# PowerTest.net
KiCad netlist of a schematic drawn in EAGLE
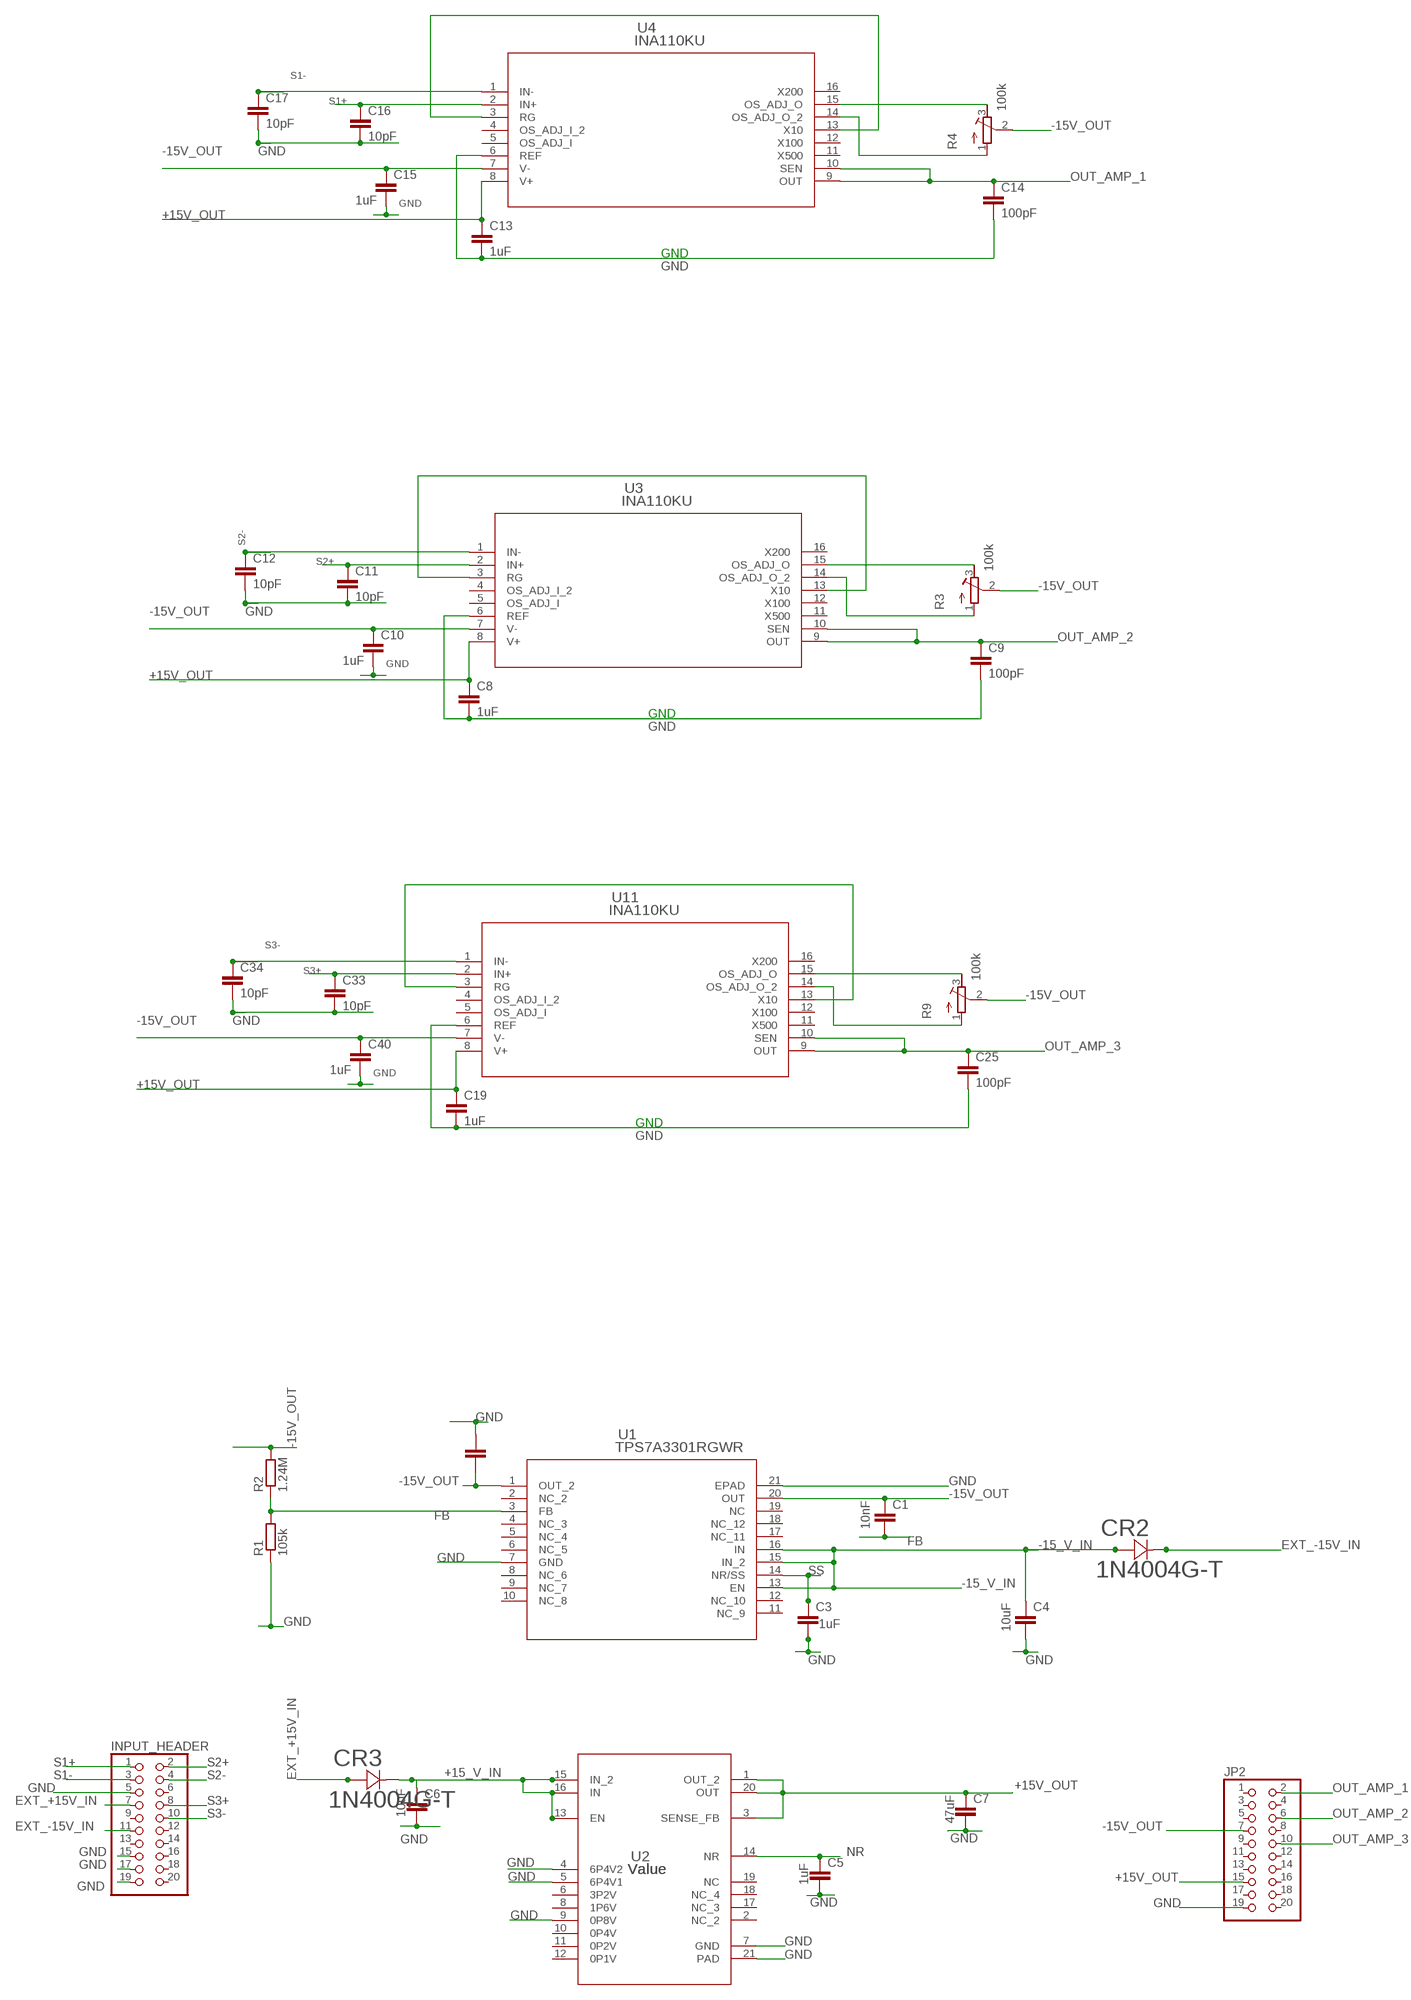
[diagram p0: schematic, sheet 1]

(export (version "E")
  (design (tool "Eeschema 10.0.6"))
  (components
    (comp (ref "C1")
      (value "10nF")
      (footprint "eagle-import:C1210")
      (libsource (lib "eagle-import") (part "C-EUC1210"))
    )
    (comp (ref "C3")
      (value "1uF")
      (footprint "eagle-import:C1210")
      (libsource (lib "eagle-import") (part "C-EUC1210"))
    )
    (comp (ref "C4")
      (value "10uF")
      (footprint "eagle-import:C1210")
      (libsource (lib "eagle-import") (part "C-EUC1210"))
    )
    (comp (ref "C5")
      (value "1uF")
      (footprint "eagle-import:C1210")
      (libsource (lib "eagle-import") (part "C-EUC1210"))
    )
    (comp (ref "C6")
      (value "10uF")
      (footprint "eagle-import:C1210")
      (libsource (lib "eagle-import") (part "C-EUC1210"))
    )
    (comp (ref "C7")
      (value "47uF")
      (footprint "eagle-import:C1210")
      (libsource (lib "eagle-import") (part "C-EUC1210"))
    )
    (comp (ref "C8")
      (value "1uF")
      (footprint "eagle-import:C1210")
      (libsource (lib "eagle-import") (part "C-EUC1210"))
    )
    (comp (ref "C9")
      (value "100pF")
      (footprint "eagle-import:C1210")
      (libsource (lib "eagle-import") (part "C-EUC1210"))
    )
    (comp (ref "C10")
      (value "1uF")
      (footprint "eagle-import:C1210")
      (libsource (lib "eagle-import") (part "C-EUC1210"))
    )
    (comp (ref "C11")
      (value "10pF")
      (footprint "eagle-import:C1210")
      (libsource (lib "eagle-import") (part "C-EUC1210"))
    )
    (comp (ref "C12")
      (value "10pF")
      (footprint "eagle-import:C1210")
      (libsource (lib "eagle-import") (part "C-EUC1210"))
    )
    (comp (ref "C13")
      (value "1uF")
      (footprint "eagle-import:C1210")
      (libsource (lib "eagle-import") (part "C-EUC1210"))
    )
    (comp (ref "C14")
      (value "100pF")
      (footprint "eagle-import:C1210")
      (libsource (lib "eagle-import") (part "C-EUC1210"))
    )
    (comp (ref "C15")
      (value "1uF")
      (footprint "eagle-import:C1210")
      (libsource (lib "eagle-import") (part "C-EUC1210"))
    )
    (comp (ref "C16")
      (value "10pF")
      (footprint "eagle-import:C1210")
      (libsource (lib "eagle-import") (part "C-EUC1210"))
    )
    (comp (ref "C17")
      (value "10pF")
      (footprint "eagle-import:C1210")
      (libsource (lib "eagle-import") (part "C-EUC1210"))
    )
    (comp (ref "C19")
      (value "1uF")
      (footprint "eagle-import:C1210")
      (libsource (lib "eagle-import") (part "C-EUC1210"))
    )
    (comp (ref "C25")
      (value "100pF")
      (footprint "eagle-import:C1210")
      (libsource (lib "eagle-import") (part "C-EUC1210"))
    )
    (comp (ref "C33")
      (value "10pF")
      (footprint "eagle-import:C1210")
      (libsource (lib "eagle-import") (part "C-EUC1210"))
    )
    (comp (ref "C34")
      (value "10pF")
      (footprint "eagle-import:C1210")
      (libsource (lib "eagle-import") (part "C-EUC1210"))
    )
    (comp (ref "C40")
      (value "1uF")
      (footprint "eagle-import:C1210")
      (libsource (lib "eagle-import") (part "C-EUC1210"))
    )
    (comp (ref "C55")
      (value "47uF")
      (footprint "eagle-import:C1210")
      (libsource (lib "eagle-import") (part "C-EUC1210"))
    )
    (comp (ref "CR2")
      (value "1N4004G-T")
      (footprint "eagle-import:DO-41")
      (fields (field (name "MANUFACTURER_PART_NUMBER") "1N4004GT"))
      (libsource (lib "eagle-import") (part "1N4004G-T"))
    )
    (comp (ref "CR3")
      (value "1N4004G-T")
      (footprint "eagle-import:DO-41")
      (fields (field (name "MANUFACTURER_PART_NUMBER") "1N4004GT"))
      (libsource (lib "eagle-import") (part "1N4004G-T"))
    )
    (comp (ref "INPUT_HEADER")
      (value "PINHD-2X10")
      (footprint "eagle-import:2X10")
      (libsource (lib "eagle-import") (part "PINHD-2X10"))
    )
    (comp (ref "JP2")
      (value "PINHD-2X10")
      (footprint "eagle-import:2X10")
      (libsource (lib "eagle-import") (part "PINHD-2X10"))
    )
    (comp (ref "R1")
      (value "105k")
      (footprint "eagle-import:RESC2012X65")
      (libsource (lib "eagle-import") (part "RCHIP-0805(2012-METRIC)_"))
    )
    (comp (ref "R2")
      (value "1.24M")
      (footprint "eagle-import:RESC2012X65")
      (libsource (lib "eagle-import") (part "RCHIP-0805(2012-METRIC)_"))
    )
    (comp (ref "R3")
      (value "100k")
      (footprint "eagle-import:RTRIM3296Y")
      (libsource (lib "eagle-import") (part "R-TRIMM3296Y"))
    )
    (comp (ref "R4")
      (value "100k")
      (footprint "eagle-import:RTRIM3296Y")
      (libsource (lib "eagle-import") (part "R-TRIMM3296Y"))
    )
    (comp (ref "R9")
      (value "100k")
      (footprint "eagle-import:RTRIM3296Y")
      (libsource (lib "eagle-import") (part "R-TRIMM3296Y"))
    )
    (comp (ref "U1")
      (value "TPS7A3301RGWR")
      (footprint "eagle-import:RGW0020A")
      (fields
        (field (name "GENERIC_PART_NUMBER") "TPS7A3301")
        (field (name "MANUFACTURER") "Texas Instruments")
      )
      (libsource (lib "eagle-import") (part "TPS7A3301RGWR"))
    )
    (comp (ref "U2")
      (value "Value")
      (footprint "eagle-import:RGW0020A")
      (fields (field (name "MANUFACTURER") "Texas Instruments") (field (name "PARTNUMBER") "TPS7A4701RGWR"))
      (libsource (lib "eagle-import") (part "TPS7A4700RGWR"))
    )
    (comp (ref "U3")
      (value "INA110KU")
      (footprint "eagle-import:SO-G16G6.9")
      (libsource (lib "eagle-import") (part "INA110KU"))
    )
    (comp (ref "U4")
      (value "INA110KU")
      (footprint "eagle-import:SO-G16G6.9")
      (libsource (lib "eagle-import") (part "INA110KU"))
    )
    (comp (ref "U11")
      (value "INA110KU")
      (footprint "eagle-import:SO-G16G6.9")
      (libsource (lib "eagle-import") (part "INA110KU"))
    )
  )
  (nets
    (net (code "1") (name "/+15V_OUT") (class "Default")
      (node (ref "C13") (pin "1") (pinfunction "1_1") (pintype "passive"))
      (node (ref "C19") (pin "1") (pinfunction "1_1") (pintype "passive"))
      (node (ref "C7") (pin "1") (pinfunction "1_1") (pintype "passive"))
      (node (ref "C8") (pin "1") (pinfunction "1_1") (pintype "passive"))
      (node (ref "JP2") (pin "15") (pinfunction "15_15") (pintype "passive"))
      (node (ref "U11") (pin "8") (pinfunction "V+_8") (pintype "power_in"))
      (node (ref "U2") (pin "1") (pinfunction "OUT_2_1") (pintype "power_in"))
      (node (ref "U2") (pin "20") (pinfunction "OUT_20") (pintype "power_in"))
      (node (ref "U2") (pin "3") (pinfunction "SENSE_FB_3") (pintype "input"))
      (node (ref "U3") (pin "8") (pinfunction "V+_8") (pintype "power_in"))
      (node (ref "U4") (pin "8") (pinfunction "V+_8") (pintype "power_in"))
    )
    (net (code "2") (name "/+15_V_IN") (class "Default")
      (node (ref "C6") (pin "1") (pinfunction "1_1") (pintype "passive"))
      (node (ref "CR3") (pin "1") (pinfunction "1_1") (pintype "passive"))
      (node (ref "U2") (pin "13") (pinfunction "EN_13") (pintype "input"))
      (node (ref "U2") (pin "15") (pinfunction "IN_2_15") (pintype "power_in"))
      (node (ref "U2") (pin "16") (pinfunction "IN_16") (pintype "power_in"))
    )
    (net (code "3") (name "/-15V_OUT") (class "Default")
      (node (ref "C1") (pin "1") (pinfunction "1_1") (pintype "passive"))
      (node (ref "C10") (pin "1") (pinfunction "1_1") (pintype "passive"))
      (node (ref "C15") (pin "1") (pinfunction "1_1") (pintype "passive"))
      (node (ref "C40") (pin "1") (pinfunction "1_1") (pintype "passive"))
      (node (ref "C55") (pin "2") (pinfunction "2_2") (pintype "passive"))
      (node (ref "JP2") (pin "7") (pinfunction "7_7") (pintype "passive"))
      (node (ref "R2") (pin "2") (pinfunction "2_2") (pintype "passive"))
      (node (ref "R3") (pin "2") (pinfunction "S_2") (pintype "passive"))
      (node (ref "R4") (pin "2") (pinfunction "S_2") (pintype "passive"))
      (node (ref "R9") (pin "2") (pinfunction "S_2") (pintype "passive"))
      (node (ref "U1") (pin "1") (pinfunction "OUT_2_1") (pintype "output"))
      (node (ref "U1") (pin "20") (pinfunction "OUT_20") (pintype "output"))
      (node (ref "U11") (pin "7") (pinfunction "V-_7") (pintype "power_in"))
      (node (ref "U3") (pin "7") (pinfunction "V-_7") (pintype "power_in"))
      (node (ref "U4") (pin "7") (pinfunction "V-_7") (pintype "power_in"))
    )
    (net (code "4") (name "/-15_V_IN") (class "Default")
      (node (ref "C4") (pin "1") (pinfunction "1_1") (pintype "passive"))
      (node (ref "CR2") (pin "2") (pinfunction "2_2") (pintype "passive"))
      (node (ref "U1") (pin "13") (pinfunction "EN_13") (pintype "passive"))
      (node (ref "U1") (pin "15") (pinfunction "IN_2_15") (pintype "input"))
      (node (ref "U1") (pin "16") (pinfunction "IN_16") (pintype "input"))
    )
    (net (code "5") (name "/EXT_+15V_IN") (class "Default")
      (node (ref "CR3") (pin "2") (pinfunction "2_2") (pintype "passive"))
      (node (ref "INPUT_HEADER") (pin "7") (pinfunction "7_7") (pintype "passive"))
    )
    (net (code "6") (name "/EXT_-15V_IN") (class "Default")
      (node (ref "CR2") (pin "1") (pinfunction "1_1") (pintype "passive"))
      (node (ref "INPUT_HEADER") (pin "11") (pinfunction "11_11") (pintype "passive"))
    )
    (net (code "7") (name "/FB") (class "Default")
      (node (ref "C1") (pin "2") (pinfunction "2_2") (pintype "passive"))
      (node (ref "R1") (pin "2") (pinfunction "2_2") (pintype "passive"))
      (node (ref "R2") (pin "1") (pinfunction "1_1") (pintype "passive"))
      (node (ref "U1") (pin "3") (pinfunction "FB_3") (pintype "passive"))
    )
    (net (code "8") (name "/GND") (class "Default")
      (node (ref "C10") (pin "2") (pinfunction "2_2") (pintype "passive"))
      (node (ref "C11") (pin "2") (pinfunction "2_2") (pintype "passive"))
      (node (ref "C12") (pin "2") (pinfunction "2_2") (pintype "passive"))
      (node (ref "C13") (pin "2") (pinfunction "2_2") (pintype "passive"))
      (node (ref "C14") (pin "2") (pinfunction "2_2") (pintype "passive"))
      (node (ref "C15") (pin "2") (pinfunction "2_2") (pintype "passive"))
      (node (ref "C16") (pin "2") (pinfunction "2_2") (pintype "passive"))
      (node (ref "C17") (pin "2") (pinfunction "2_2") (pintype "passive"))
      (node (ref "C19") (pin "2") (pinfunction "2_2") (pintype "passive"))
      (node (ref "C25") (pin "2") (pinfunction "2_2") (pintype "passive"))
      (node (ref "C3") (pin "2") (pinfunction "2_2") (pintype "passive"))
      (node (ref "C33") (pin "2") (pinfunction "2_2") (pintype "passive"))
      (node (ref "C34") (pin "2") (pinfunction "2_2") (pintype "passive"))
      (node (ref "C4") (pin "2") (pinfunction "2_2") (pintype "passive"))
      (node (ref "C40") (pin "2") (pinfunction "2_2") (pintype "passive"))
      (node (ref "C5") (pin "2") (pinfunction "2_2") (pintype "passive"))
      (node (ref "C55") (pin "1") (pinfunction "1_1") (pintype "passive"))
      (node (ref "C6") (pin "2") (pinfunction "2_2") (pintype "passive"))
      (node (ref "C7") (pin "2") (pinfunction "2_2") (pintype "passive"))
      (node (ref "C8") (pin "2") (pinfunction "2_2") (pintype "passive"))
      (node (ref "C9") (pin "2") (pinfunction "2_2") (pintype "passive"))
      (node (ref "INPUT_HEADER") (pin "15") (pinfunction "15_15") (pintype "passive"))
      (node (ref "INPUT_HEADER") (pin "17") (pinfunction "17_17") (pintype "passive"))
      (node (ref "INPUT_HEADER") (pin "19") (pinfunction "19_19") (pintype "passive"))
      (node (ref "INPUT_HEADER") (pin "5") (pinfunction "5_5") (pintype "passive"))
      (node (ref "JP2") (pin "19") (pinfunction "19_19") (pintype "passive"))
      (node (ref "R1") (pin "1") (pinfunction "1_1") (pintype "passive"))
      (node (ref "U1") (pin "21") (pinfunction "EPAD_21") (pintype "passive"))
      (node (ref "U1") (pin "7") (pinfunction "GND_7") (pintype "power_in"))
      (node (ref "U11") (pin "6") (pinfunction "REF_6") (pintype "input"))
      (node (ref "U2") (pin "21") (pinfunction "PAD_21") (pintype "passive"))
      (node (ref "U2") (pin "4") (pinfunction "6P4V2_4") (pintype "passive"))
      (node (ref "U2") (pin "5") (pinfunction "6P4V1_5") (pintype "passive"))
      (node (ref "U2") (pin "7") (pinfunction "GND_7") (pintype "power_in"))
      (node (ref "U2") (pin "9") (pinfunction "0P8V_9") (pintype "passive"))
      (node (ref "U3") (pin "6") (pinfunction "REF_6") (pintype "input"))
      (node (ref "U4") (pin "6") (pinfunction "REF_6") (pintype "input"))
    )
    (net (code "9") (name "/NR") (class "Default")
      (node (ref "C5") (pin "1") (pinfunction "1_1") (pintype "passive"))
      (node (ref "U2") (pin "14") (pinfunction "NR_14") (pintype "input"))
    )
    (net (code "10") (name "/OUT_AMP_1") (class "Default")
      (node (ref "C14") (pin "1") (pinfunction "1_1") (pintype "passive"))
      (node (ref "JP2") (pin "2") (pinfunction "2_2") (pintype "passive"))
      (node (ref "U4") (pin "10") (pinfunction "SEN_10") (pintype "input"))
      (node (ref "U4") (pin "9") (pinfunction "OUT_9") (pintype "output"))
    )
    (net (code "11") (name "/OUT_AMP_2") (class "Default")
      (node (ref "C9") (pin "1") (pinfunction "1_1") (pintype "passive"))
      (node (ref "JP2") (pin "6") (pinfunction "6_6") (pintype "passive"))
      (node (ref "U3") (pin "10") (pinfunction "SEN_10") (pintype "input"))
      (node (ref "U3") (pin "9") (pinfunction "OUT_9") (pintype "output"))
    )
    (net (code "12") (name "/OUT_AMP_3") (class "Default")
      (node (ref "C25") (pin "1") (pinfunction "1_1") (pintype "passive"))
      (node (ref "JP2") (pin "10") (pinfunction "10_10") (pintype "passive"))
      (node (ref "U11") (pin "10") (pinfunction "SEN_10") (pintype "input"))
      (node (ref "U11") (pin "9") (pinfunction "OUT_9") (pintype "output"))
    )
    (net (code "13") (name "/S1+") (class "Default")
      (node (ref "C16") (pin "1") (pinfunction "1_1") (pintype "passive"))
      (node (ref "INPUT_HEADER") (pin "1") (pinfunction "1_1") (pintype "passive"))
      (node (ref "U4") (pin "2") (pinfunction "IN+_2") (pintype "input"))
    )
    (net (code "14") (name "/S1-") (class "Default")
      (node (ref "C17") (pin "1") (pinfunction "1_1") (pintype "passive"))
      (node (ref "INPUT_HEADER") (pin "3") (pinfunction "3_3") (pintype "passive"))
      (node (ref "U4") (pin "1") (pinfunction "IN-_1") (pintype "input"))
    )
    (net (code "15") (name "/S2+") (class "Default")
      (node (ref "C11") (pin "1") (pinfunction "1_1") (pintype "passive"))
      (node (ref "INPUT_HEADER") (pin "2") (pinfunction "2_2") (pintype "passive"))
      (node (ref "U3") (pin "2") (pinfunction "IN+_2") (pintype "input"))
    )
    (net (code "16") (name "/S2-") (class "Default")
      (node (ref "C12") (pin "1") (pinfunction "1_1") (pintype "passive"))
      (node (ref "INPUT_HEADER") (pin "4") (pinfunction "4_4") (pintype "passive"))
      (node (ref "U3") (pin "1") (pinfunction "IN-_1") (pintype "input"))
    )
    (net (code "17") (name "/S3+") (class "Default")
      (node (ref "C33") (pin "1") (pinfunction "1_1") (pintype "passive"))
      (node (ref "INPUT_HEADER") (pin "8") (pinfunction "8_8") (pintype "passive"))
      (node (ref "U11") (pin "2") (pinfunction "IN+_2") (pintype "input"))
    )
    (net (code "18") (name "/S3-") (class "Default")
      (node (ref "C34") (pin "1") (pinfunction "1_1") (pintype "passive"))
      (node (ref "INPUT_HEADER") (pin "10") (pinfunction "10_10") (pintype "passive"))
      (node (ref "U11") (pin "1") (pinfunction "IN-_1") (pintype "input"))
    )
    (net (code "19") (name "/SS") (class "Default")
      (node (ref "C3") (pin "1") (pinfunction "1_1") (pintype "passive"))
      (node (ref "U1") (pin "14") (pinfunction "NR/SS_14") (pintype "passive"))
    )
    (net (code "20") (name "Net-(R3-A)") (class "Default")
      (node (ref "R3") (pin "1") (pinfunction "A_1") (pintype "passive"))
      (node (ref "U3") (pin "14") (pinfunction "OS_ADJ_O_2_14") (pintype "passive"))
    )
    (net (code "21") (name "Net-(R3-E)") (class "Default")
      (node (ref "R3") (pin "3") (pinfunction "E_3") (pintype "passive"))
      (node (ref "U3") (pin "15") (pinfunction "OS_ADJ_O_15") (pintype "passive"))
    )
    (net (code "22") (name "Net-(R4-A)") (class "Default")
      (node (ref "R4") (pin "1") (pinfunction "A_1") (pintype "passive"))
      (node (ref "U4") (pin "14") (pinfunction "OS_ADJ_O_2_14") (pintype "passive"))
    )
    (net (code "23") (name "Net-(R4-E)") (class "Default")
      (node (ref "R4") (pin "3") (pinfunction "E_3") (pintype "passive"))
      (node (ref "U4") (pin "15") (pinfunction "OS_ADJ_O_15") (pintype "passive"))
    )
    (net (code "24") (name "Net-(R9-A)") (class "Default")
      (node (ref "R9") (pin "1") (pinfunction "A_1") (pintype "passive"))
      (node (ref "U11") (pin "14") (pinfunction "OS_ADJ_O_2_14") (pintype "passive"))
    )
    (net (code "25") (name "Net-(R9-E)") (class "Default")
      (node (ref "R9") (pin "3") (pinfunction "E_3") (pintype "passive"))
      (node (ref "U11") (pin "15") (pinfunction "OS_ADJ_O_15") (pintype "passive"))
    )
    (net (code "26") (name "Net-(U3-RG)") (class "Default")
      (node (ref "U3") (pin "13") (pinfunction "X10_13") (pintype "passive"))
      (node (ref "U3") (pin "3") (pinfunction "RG_3") (pintype "input"))
    )
    (net (code "27") (name "Net-(U4-RG)") (class "Default")
      (node (ref "U4") (pin "13") (pinfunction "X10_13") (pintype "passive"))
      (node (ref "U4") (pin "3") (pinfunction "RG_3") (pintype "input"))
    )
    (net (code "28") (name "Net-(U11-RG)") (class "Default")
      (node (ref "U11") (pin "13") (pinfunction "X10_13") (pintype "passive"))
      (node (ref "U11") (pin "3") (pinfunction "RG_3") (pintype "input"))
    )
    (net (code "29") (name "unconnected-(INPUT_HEADER-Pad6)") (class "Default")
      (node (ref "INPUT_HEADER") (pin "6") (pinfunction "6_6") (pintype "passive"))
    )
    (net (code "30") (name "unconnected-(INPUT_HEADER-Pad9)") (class "Default")
      (node (ref "INPUT_HEADER") (pin "9") (pinfunction "9_9") (pintype "passive"))
    )
    (net (code "31") (name "unconnected-(INPUT_HEADER-Pad12)") (class "Default")
      (node (ref "INPUT_HEADER") (pin "12") (pinfunction "12_12") (pintype "passive"))
    )
    (net (code "32") (name "unconnected-(INPUT_HEADER-Pad13)") (class "Default")
      (node (ref "INPUT_HEADER") (pin "13") (pinfunction "13_13") (pintype "passive"))
    )
    (net (code "33") (name "unconnected-(INPUT_HEADER-Pad14)") (class "Default")
      (node (ref "INPUT_HEADER") (pin "14") (pinfunction "14_14") (pintype "passive"))
    )
    (net (code "34") (name "unconnected-(INPUT_HEADER-Pad16)") (class "Default")
      (node (ref "INPUT_HEADER") (pin "16") (pinfunction "16_16") (pintype "passive"))
    )
    (net (code "35") (name "unconnected-(INPUT_HEADER-Pad18)") (class "Default")
      (node (ref "INPUT_HEADER") (pin "18") (pinfunction "18_18") (pintype "passive"))
    )
    (net (code "36") (name "unconnected-(INPUT_HEADER-Pad20)") (class "Default")
      (node (ref "INPUT_HEADER") (pin "20") (pinfunction "20_20") (pintype "passive"))
    )
    (net (code "37") (name "unconnected-(JP2-Pad1)") (class "Default")
      (node (ref "JP2") (pin "1") (pinfunction "1_1") (pintype "passive"))
    )
    (net (code "38") (name "unconnected-(JP2-Pad3)") (class "Default")
      (node (ref "JP2") (pin "3") (pinfunction "3_3") (pintype "passive"))
    )
    (net (code "39") (name "unconnected-(JP2-Pad4)") (class "Default")
      (node (ref "JP2") (pin "4") (pinfunction "4_4") (pintype "passive"))
    )
    (net (code "40") (name "unconnected-(JP2-Pad5)") (class "Default")
      (node (ref "JP2") (pin "5") (pinfunction "5_5") (pintype "passive"))
    )
    (net (code "41") (name "unconnected-(JP2-Pad8)") (class "Default")
      (node (ref "JP2") (pin "8") (pinfunction "8_8") (pintype "passive"))
    )
    (net (code "42") (name "unconnected-(JP2-Pad9)") (class "Default")
      (node (ref "JP2") (pin "9") (pinfunction "9_9") (pintype "passive"))
    )
    (net (code "43") (name "unconnected-(JP2-Pad11)") (class "Default")
      (node (ref "JP2") (pin "11") (pinfunction "11_11") (pintype "passive"))
    )
    (net (code "44") (name "unconnected-(JP2-Pad12)") (class "Default")
      (node (ref "JP2") (pin "12") (pinfunction "12_12") (pintype "passive"))
    )
    (net (code "45") (name "unconnected-(JP2-Pad13)") (class "Default")
      (node (ref "JP2") (pin "13") (pinfunction "13_13") (pintype "passive"))
    )
    (net (code "46") (name "unconnected-(JP2-Pad14)") (class "Default")
      (node (ref "JP2") (pin "14") (pinfunction "14_14") (pintype "passive"))
    )
    (net (code "47") (name "unconnected-(JP2-Pad16)") (class "Default")
      (node (ref "JP2") (pin "16") (pinfunction "16_16") (pintype "passive"))
    )
    (net (code "48") (name "unconnected-(JP2-Pad17)") (class "Default")
      (node (ref "JP2") (pin "17") (pinfunction "17_17") (pintype "passive"))
    )
    (net (code "49") (name "unconnected-(JP2-Pad18)") (class "Default")
      (node (ref "JP2") (pin "18") (pinfunction "18_18") (pintype "passive"))
    )
    (net (code "50") (name "unconnected-(JP2-Pad20)") (class "Default")
      (node (ref "JP2") (pin "20") (pinfunction "20_20") (pintype "passive"))
    )
    (net (code "51") (name "unconnected-(U1-NC-Pad19)") (class "Default")
      (node (ref "U1") (pin "19") (pinfunction "NC_19") (pintype "passive"))
    )
    (net (code "52") (name "unconnected-(U1-NC_2-Pad2)") (class "Default")
      (node (ref "U1") (pin "2") (pinfunction "NC_2_2") (pintype "passive"))
    )
    (net (code "53") (name "unconnected-(U1-NC_3-Pad4)") (class "Default")
      (node (ref "U1") (pin "4") (pinfunction "NC_3_4") (pintype "passive"))
    )
    (net (code "54") (name "unconnected-(U1-NC_4-Pad5)") (class "Default")
      (node (ref "U1") (pin "5") (pinfunction "NC_4_5") (pintype "passive"))
    )
    (net (code "55") (name "unconnected-(U1-NC_5-Pad6)") (class "Default")
      (node (ref "U1") (pin "6") (pinfunction "NC_5_6") (pintype "passive"))
    )
    (net (code "56") (name "unconnected-(U1-NC_6-Pad8)") (class "Default")
      (node (ref "U1") (pin "8") (pinfunction "NC_6_8") (pintype "passive"))
    )
    (net (code "57") (name "unconnected-(U1-NC_7-Pad9)") (class "Default")
      (node (ref "U1") (pin "9") (pinfunction "NC_7_9") (pintype "passive"))
    )
    (net (code "58") (name "unconnected-(U1-NC_8-Pad10)") (class "Default")
      (node (ref "U1") (pin "10") (pinfunction "NC_8_10") (pintype "passive"))
    )
    (net (code "59") (name "unconnected-(U1-NC_9-Pad11)") (class "Default")
      (node (ref "U1") (pin "11") (pinfunction "NC_9_11") (pintype "passive"))
    )
    (net (code "60") (name "unconnected-(U1-NC_10-Pad12)") (class "Default")
      (node (ref "U1") (pin "12") (pinfunction "NC_10_12") (pintype "passive"))
    )
    (net (code "61") (name "unconnected-(U1-NC_11-Pad17)") (class "Default")
      (node (ref "U1") (pin "17") (pinfunction "NC_11_17") (pintype "passive"))
    )
    (net (code "62") (name "unconnected-(U1-NC_12-Pad18)") (class "Default")
      (node (ref "U1") (pin "18") (pinfunction "NC_12_18") (pintype "passive"))
    )
    (net (code "63") (name "unconnected-(U2-0P1V-Pad12)") (class "Default")
      (node (ref "U2") (pin "12") (pinfunction "0P1V_12") (pintype "passive"))
    )
    (net (code "64") (name "unconnected-(U2-0P2V-Pad11)") (class "Default")
      (node (ref "U2") (pin "11") (pinfunction "0P2V_11") (pintype "passive"))
    )
    (net (code "65") (name "unconnected-(U2-0P4V-Pad10)") (class "Default")
      (node (ref "U2") (pin "10") (pinfunction "0P4V_10") (pintype "passive"))
    )
    (net (code "66") (name "unconnected-(U2-1P6V-Pad8)") (class "Default")
      (node (ref "U2") (pin "8") (pinfunction "1P6V_8") (pintype "passive"))
    )
    (net (code "67") (name "unconnected-(U2-3P2V-Pad6)") (class "Default")
      (node (ref "U2") (pin "6") (pinfunction "3P2V_6") (pintype "passive"))
    )
    (net (code "68") (name "unconnected-(U2-NC-Pad19)") (class "Default")
      (node (ref "U2") (pin "19") (pinfunction "NC_19") (pintype "passive"))
    )
    (net (code "69") (name "unconnected-(U2-NC_2-Pad2)") (class "Default")
      (node (ref "U2") (pin "2") (pinfunction "NC_2_2") (pintype "passive"))
    )
    (net (code "70") (name "unconnected-(U2-NC_3-Pad17)") (class "Default")
      (node (ref "U2") (pin "17") (pinfunction "NC_3_17") (pintype "passive"))
    )
    (net (code "71") (name "unconnected-(U2-NC_4-Pad18)") (class "Default")
      (node (ref "U2") (pin "18") (pinfunction "NC_4_18") (pintype "passive"))
    )
    (net (code "72") (name "unconnected-(U3-OS_ADJ_I-Pad5)") (class "Default")
      (node (ref "U3") (pin "5") (pinfunction "OS_ADJ_I_5") (pintype "passive"))
    )
    (net (code "73") (name "unconnected-(U3-OS_ADJ_I_2-Pad4)") (class "Default")
      (node (ref "U3") (pin "4") (pinfunction "OS_ADJ_I_2_4") (pintype "passive"))
    )
    (net (code "74") (name "unconnected-(U3-X100-Pad12)") (class "Default")
      (node (ref "U3") (pin "12") (pinfunction "X100_12") (pintype "passive"))
    )
    (net (code "75") (name "unconnected-(U3-X200-Pad16)") (class "Default")
      (node (ref "U3") (pin "16") (pinfunction "X200_16") (pintype "passive"))
    )
    (net (code "76") (name "unconnected-(U3-X500-Pad11)") (class "Default")
      (node (ref "U3") (pin "11") (pinfunction "X500_11") (pintype "passive"))
    )
    (net (code "77") (name "unconnected-(U4-OS_ADJ_I-Pad5)") (class "Default")
      (node (ref "U4") (pin "5") (pinfunction "OS_ADJ_I_5") (pintype "passive"))
    )
    (net (code "78") (name "unconnected-(U4-OS_ADJ_I_2-Pad4)") (class "Default")
      (node (ref "U4") (pin "4") (pinfunction "OS_ADJ_I_2_4") (pintype "passive"))
    )
    (net (code "79") (name "unconnected-(U4-X100-Pad12)") (class "Default")
      (node (ref "U4") (pin "12") (pinfunction "X100_12") (pintype "passive"))
    )
    (net (code "80") (name "unconnected-(U4-X200-Pad16)") (class "Default")
      (node (ref "U4") (pin "16") (pinfunction "X200_16") (pintype "passive"))
    )
    (net (code "81") (name "unconnected-(U4-X500-Pad11)") (class "Default")
      (node (ref "U4") (pin "11") (pinfunction "X500_11") (pintype "passive"))
    )
    (net (code "82") (name "unconnected-(U11-OS_ADJ_I-Pad5)") (class "Default")
      (node (ref "U11") (pin "5") (pinfunction "OS_ADJ_I_5") (pintype "passive"))
    )
    (net (code "83") (name "unconnected-(U11-OS_ADJ_I_2-Pad4)") (class "Default")
      (node (ref "U11") (pin "4") (pinfunction "OS_ADJ_I_2_4") (pintype "passive"))
    )
    (net (code "84") (name "unconnected-(U11-X100-Pad12)") (class "Default")
      (node (ref "U11") (pin "12") (pinfunction "X100_12") (pintype "passive"))
    )
    (net (code "85") (name "unconnected-(U11-X200-Pad16)") (class "Default")
      (node (ref "U11") (pin "16") (pinfunction "X200_16") (pintype "passive"))
    )
    (net (code "86") (name "unconnected-(U11-X500-Pad11)") (class "Default")
      (node (ref "U11") (pin "11") (pinfunction "X500_11") (pintype "passive"))
    )
  )
)
